# 03_-_Sensors.net
KiCad netlist of a schematic drawn in Altium Designer
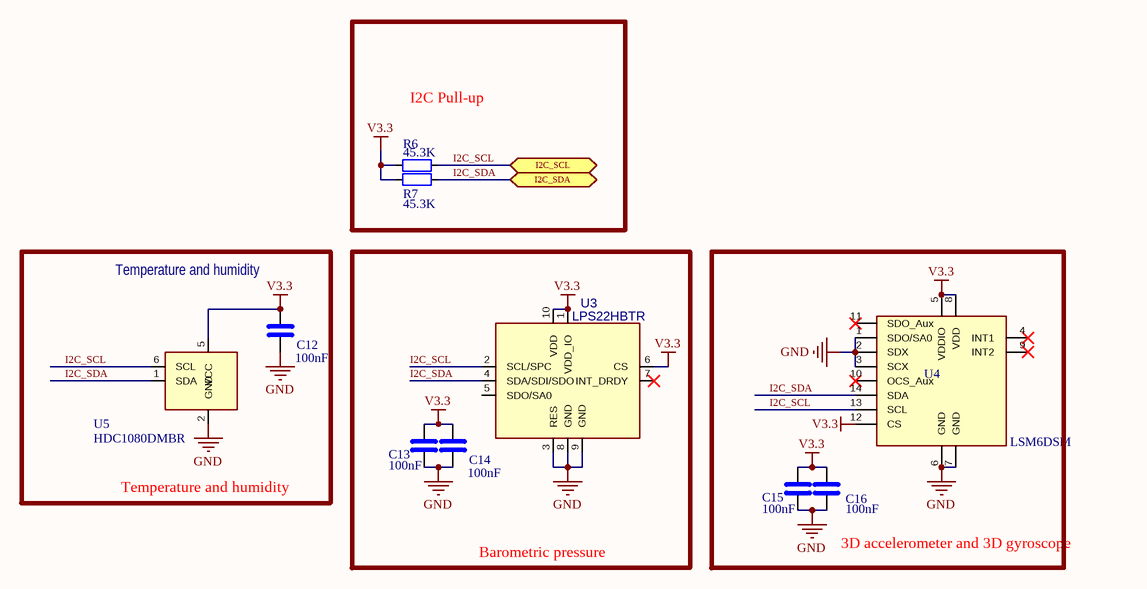
[diagram p0: 03 - Sensors.SchDoc]

(export (version "E")
  (design (tool "Eeschema 10.0.6"))
  (components
    (comp (ref "C12")
      (value "100nF")
      (footprint "CAP_0603")
      (fields (field (name "LCSC PART") "C6119867"))
      (libsource (lib "WalterFeels") (part "C"))
    )
    (comp (ref "C13")
      (value "100nF")
      (footprint "CAP_0603")
      (fields (field (name "LCSC PART") "C6119867"))
      (libsource (lib "WalterFeels") (part "C"))
    )
    (comp (ref "C14")
      (value "100nF")
      (footprint "CAP_0603")
      (fields (field (name "LCSC PART") "C6119867"))
      (libsource (lib "WalterFeels") (part "C"))
    )
    (comp (ref "C15")
      (value "100nF")
      (footprint "CAP_0603")
      (fields (field (name "LCSC PART") "C6119867"))
      (libsource (lib "WalterFeels") (part "C"))
    )
    (comp (ref "C16")
      (value "100nF")
      (footprint "CAP_0603")
      (fields (field (name "LCSC PART") "C6119867"))
      (libsource (lib "WalterFeels") (part "C"))
    )
    (comp (ref "R6")
      (value "45.3K")
      (footprint "RES_0603")
      (fields (field (name "LCSC PART") "C23058"))
      (libsource (lib "Device") (part "R"))
    )
    (comp (ref "R7")
      (value "45.3K")
      (footprint "RES_0603")
      (fields (field (name "LCSC PART") "C23058"))
      (libsource (lib "Device") (part "R"))
    )
    (comp (ref "U3")
      (value "LPS22HBTR")
      (footprint "HLGA10_2X2_STM-L")
      (description "26Kpa~126Kpa HLGA-10(2x2) Pressure Sensors ROHS")
      (fields (field (name "LCSC PART") "C2827824") (field (name "Comment") "LPS22HH"))
      (libsource (lib "WalterFeels") (part "LPS22HBTR"))
    )
    (comp (ref "U4")
      (value "LSM6DSM")
      (footprint "LGA-14_3x2.5mm_P0.5mm_LayoutBorder3x4y")
      (fields (field (name "LCSC PART") "C94048"))
      (libsource (lib "WalterFeels") (part "LSM6DSM"))
    )
    (comp (ref "U5")
      (value "HDC1080DMBR")
      (footprint "Texas_PWSON-N6")
      (fields (field (name "LCSC PART") "C82227"))
      (libsource (lib "Sensor_Humidity") (part "HDC1080"))
    )
  )
  (nets
    (net (code "1") (name "/I2C_SCL") (class "Default")
      (node (ref "R6") (pin "1") (pinfunction "1_1") (pintype "passive"))
      (node (ref "U3") (pin "2") (pinfunction "SCL/SPC_2") (pintype "passive"))
      (node (ref "U4") (pin "13") (pinfunction "SCL_13") (pintype "passive"))
      (node (ref "U5") (pin "6") (pinfunction "SCL_6") (pintype "passive"))
    )
    (net (code "2") (name "/I2C_SDA") (class "Default")
      (node (ref "R7") (pin "1") (pinfunction "1_1") (pintype "passive"))
      (node (ref "U3") (pin "4") (pinfunction "SDA/SDI/SDO_4") (pintype "passive"))
      (node (ref "U4") (pin "14") (pinfunction "SDA_14") (pintype "passive"))
      (node (ref "U5") (pin "1") (pinfunction "SDA_1") (pintype "passive"))
    )
    (net (code "3") (name "GND") (class "Default")
      (node (ref "C12") (pin "2") (pinfunction "2_2") (pintype "passive"))
      (node (ref "C13") (pin "2") (pinfunction "2_2") (pintype "passive"))
      (node (ref "C14") (pin "2") (pinfunction "2_2") (pintype "passive"))
      (node (ref "C15") (pin "2") (pinfunction "2_2") (pintype "passive"))
      (node (ref "C16") (pin "2") (pinfunction "2_2") (pintype "passive"))
      (node (ref "U3") (pin "3") (pinfunction "RES_3") (pintype "passive"))
      (node (ref "U3") (pin "8") (pinfunction "GND_8") (pintype "passive"))
      (node (ref "U3") (pin "9") (pinfunction "GND_9") (pintype "passive"))
      (node (ref "U4") (pin "1") (pinfunction "SDO/SA0_1") (pintype "passive"))
      (node (ref "U4") (pin "2") (pinfunction "SDX_2") (pintype "passive"))
      (node (ref "U4") (pin "3") (pinfunction "SCX_3") (pintype "passive"))
      (node (ref "U4") (pin "6") (pinfunction "GND_6") (pintype "passive"))
      (node (ref "U4") (pin "7") (pinfunction "GND_7") (pintype "passive"))
      (node (ref "U5") (pin "2") (pinfunction "GND_2") (pintype "passive"))
    )
    (net (code "4") (name "V3.3") (class "Default")
      (node (ref "C12") (pin "1") (pinfunction "1_1") (pintype "passive"))
      (node (ref "C13") (pin "1") (pinfunction "1_1") (pintype "passive"))
      (node (ref "C14") (pin "1") (pinfunction "1_1") (pintype "passive"))
      (node (ref "C15") (pin "1") (pinfunction "1_1") (pintype "passive"))
      (node (ref "C16") (pin "1") (pinfunction "1_1") (pintype "passive"))
      (node (ref "R6") (pin "2") (pinfunction "2_2") (pintype "passive"))
      (node (ref "R7") (pin "2") (pinfunction "2_2") (pintype "passive"))
      (node (ref "U3") (pin "1") (pinfunction "VDD_IO_1") (pintype "passive"))
      (node (ref "U3") (pin "10") (pinfunction "VDD_10") (pintype "passive"))
      (node (ref "U3") (pin "6") (pinfunction "CS_6") (pintype "passive"))
      (node (ref "U4") (pin "12") (pinfunction "CS_12") (pintype "passive"))
      (node (ref "U4") (pin "5") (pinfunction "VDDIO_5") (pintype "passive"))
      (node (ref "U4") (pin "8") (pinfunction "VDD_8") (pintype "passive"))
      (node (ref "U5") (pin "5") (pinfunction "VCC_5") (pintype "passive"))
    )
    (net (code "5") (name "unconnected-(U3-INT_DRDY-Pad7)") (class "Default")
      (node (ref "U3") (pin "7") (pinfunction "INT_DRDY_7") (pintype "passive+no_connect"))
    )
    (net (code "6") (name "unconnected-(U3-SDO{slash}SA0-Pad5)") (class "Default")
      (node (ref "U3") (pin "5") (pinfunction "SDO/SA0_5") (pintype "passive"))
    )
    (net (code "7") (name "unconnected-(U4-INT1-Pad4)") (class "Default")
      (node (ref "U4") (pin "4") (pinfunction "INT1_4") (pintype "passive+no_connect"))
    )
    (net (code "8") (name "unconnected-(U4-INT2-Pad9)") (class "Default")
      (node (ref "U4") (pin "9") (pinfunction "INT2_9") (pintype "passive+no_connect"))
    )
    (net (code "9") (name "unconnected-(U4-OCS_Aux-Pad10)") (class "Default")
      (node (ref "U4") (pin "10") (pinfunction "OCS_Aux_10") (pintype "passive+no_connect"))
    )
    (net (code "10") (name "unconnected-(U4-SDO_Aux-Pad11)") (class "Default")
      (node (ref "U4") (pin "11") (pinfunction "SDO_Aux_11") (pintype "passive+no_connect"))
    )
    (net (code "11") (name "unconnected-(U5-DAP-Pad7)") (class "Default")
      (node (ref "U5") (pin "7") (pinfunction "DAP_7") (pintype "passive"))
    )
    (net (code "12") (name "unconnected-(U5-NC-Pad3)") (class "Default")
      (node (ref "U5") (pin "3") (pinfunction "NC_3") (pintype "passive"))
    )
    (net (code "13") (name "unconnected-(U5-NC-Pad4)") (class "Default")
      (node (ref "U5") (pin "4") (pinfunction "NC_4") (pintype "passive"))
    )
  )
)
